# Amis-esp8266d.net
KiCad netlist of a schematic drawn in EAGLE
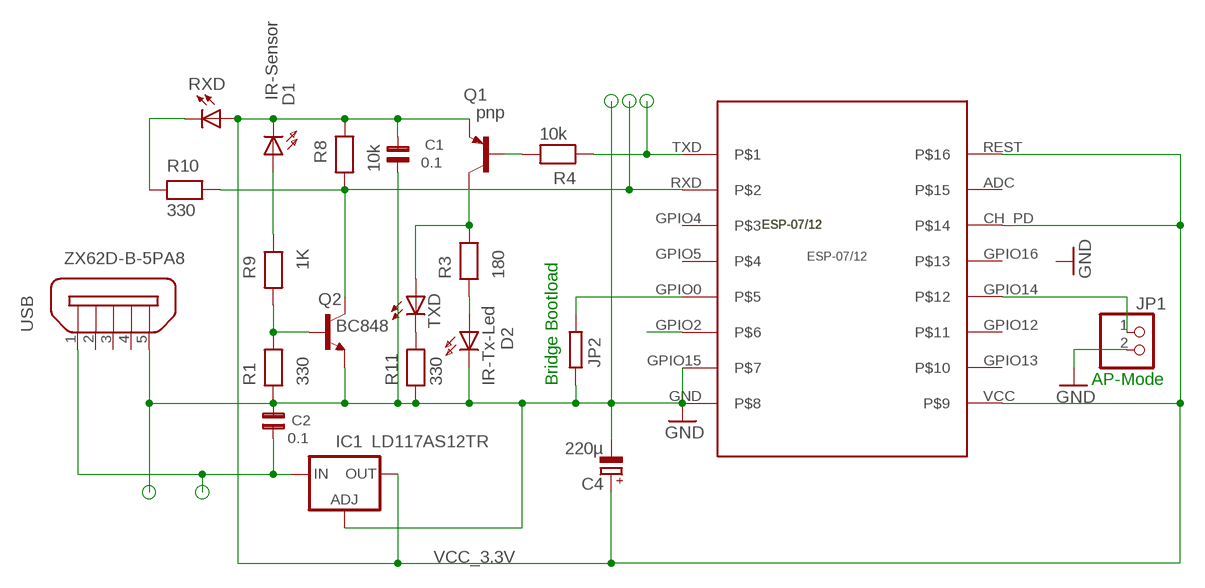
[diagram p0: schematic, sheet 1]

(export (version "E")
  (design (tool "Eeschema 10.0.6"))
  (components
    (comp (ref "C1")
      (value "0.1")
      (footprint "eagle-import:0805W")
      (libsource (lib "eagle-import") (part "C0805W"))
    )
    (comp (ref "C2")
      (value "0.1")
      (footprint "eagle-import:0805W")
      (libsource (lib "eagle-import") (part "C0805W"))
    )
    (comp (ref "C4")
      (value "220µ")
      (footprint "eagle-import:153CLV-0605")
      (libsource (lib "eagle-import") (part "CPOL-EU153CLV-0605"))
    )
    (comp (ref "D1")
      (value "IR-Sensor")
      (footprint "eagle-import:HSMXC670")
      (libsource (lib "eagle-import") (part "HSMXC670"))
    )
    (comp (ref "D2")
      (value "IR-Tx-Led")
      (footprint "eagle-import:HSMXC670")
      (libsource (lib "eagle-import") (part "HSMXC670"))
    )
    (comp (ref "IC1")
      (value "LD117AS12TR")
      (footprint "eagle-import:SOT223")
      (libsource (lib "eagle-import") (part "LD117A?S12TR"))
    )
    (comp (ref "JP1")
      (value "PINHD-1X2")
      (footprint "eagle-import:1X02")
      (libsource (lib "eagle-import") (part "PINHD-1X2"))
    )
    (comp (ref "JP2")
      (value "R-EU_R1210W")
      (footprint "eagle-import:R1210W")
      (libsource (lib "eagle-import") (part "R-EU_R1210W"))
    )
    (comp (ref "Q1")
      (value "pnp")
      (footprint "eagle-import:SOT23")
      (libsource (lib "eagle-import") (part "-?SOT23MMBTA56"))
    )
    (comp (ref "Q2")
      (value "BC848")
      (footprint "eagle-import:SOT23")
      (libsource (lib "eagle-import") (part "BC848"))
    )
    (comp (ref "R1")
      (value "330")
      (footprint "eagle-import:0805W")
      (libsource (lib "eagle-import") (part "R0805W"))
    )
    (comp (ref "R3")
      (value "180")
      (footprint "eagle-import:0805W")
      (libsource (lib "eagle-import") (part "R0805W"))
    )
    (comp (ref "R4")
      (value "10k")
      (footprint "eagle-import:0805W")
      (libsource (lib "eagle-import") (part "R0805W"))
    )
    (comp (ref "R8")
      (value "10k")
      (footprint "eagle-import:0805W")
      (libsource (lib "eagle-import") (part "R0805W"))
    )
    (comp (ref "R9")
      (value "1K")
      (footprint "eagle-import:0805W")
      (libsource (lib "eagle-import") (part "R0805W"))
    )
    (comp (ref "R10")
      (value "330")
      (footprint "eagle-import:0805W")
      (libsource (lib "eagle-import") (part "R0805W"))
    )
    (comp (ref "R11")
      (value "330")
      (footprint "eagle-import:0805W")
      (libsource (lib "eagle-import") (part "R0805W"))
    )
    (comp (ref "RXD")
      (value "LEDSML0805")
      (footprint "eagle-import:SML0805")
      (libsource (lib "eagle-import") (part "LEDSML0805"))
    )
    (comp (ref "TXD")
      (value "LEDSML0805")
      (footprint "eagle-import:SML0805")
      (libsource (lib "eagle-import") (part "LEDSML0805"))
    )
    (comp (ref "U$2")
      (value "ESP-07/12")
      (footprint "eagle-import:ESP-07_12")
      (libsource (lib "eagle-import") (part "ESP-07/12"))
    )
    (comp (ref "USB")
      (value "ZX62D-B-5PA8")
      (footprint "eagle-import:ZX62D-B-5PA8")
      (fields (field (name "MF") "Hirose"))
      (libsource (lib "eagle-import") (part "ZX62D-B-5PA8"))
    )
  )
  (nets
    (net (code "1") (name "/VCC_3.3V") (class "Default")
      (node (ref "C1") (pin "2") (pinfunction "2_2") (pintype "passive"))
      (node (ref "C4") (pin "+") (pinfunction "+_+") (pintype "passive"))
      (node (ref "D1") (pin "K") (pinfunction "C_K") (pintype "passive"))
      (node (ref "IC1") (pin "4") (pinfunction "OUT_4") (pintype "passive"))
      (node (ref "Q1") (pin "2") (pinfunction "E_2") (pintype "passive"))
      (node (ref "R8") (pin "2") (pinfunction "2_2") (pintype "passive"))
      (node (ref "RXD") (pin "A") (pinfunction "A_A") (pintype "passive"))
      (node (ref "U$2") (pin "CH_PD") (pinfunction "P$14_CH_PD") (pintype "bidirectional"))
      (node (ref "U$2") (pin "REST") (pinfunction "P$16_REST") (pintype "bidirectional"))
      (node (ref "U$2") (pin "VCC") (pinfunction "P$9_VCC") (pintype "bidirectional"))
    )
    (net (code "2") (name "GND") (class "Default")
      (node (ref "C1") (pin "1") (pinfunction "1_1") (pintype "passive"))
      (node (ref "C2") (pin "2") (pinfunction "2_2") (pintype "passive"))
      (node (ref "C4") (pin "-") (pinfunction "-_-") (pintype "passive"))
      (node (ref "D2") (pin "K") (pinfunction "C_K") (pintype "passive"))
      (node (ref "IC1") (pin "1") (pinfunction "ADJ_1") (pintype "input"))
      (node (ref "JP1") (pin "2") (pinfunction "2_2") (pintype "passive"))
      (node (ref "JP2") (pin "1") (pinfunction "1_1") (pintype "passive"))
      (node (ref "Q2") (pin "2") (pinfunction "E_2") (pintype "passive"))
      (node (ref "R1") (pin "1") (pinfunction "1_1") (pintype "passive"))
      (node (ref "R11") (pin "1") (pinfunction "1_1") (pintype "passive"))
      (node (ref "U$2") (pin "GND") (pinfunction "P$8_GND") (pintype "bidirectional"))
      (node (ref "U$2") (pin "GPIO15") (pinfunction "P$7_GPIO15") (pintype "bidirectional"))
      (node (ref "USB") (pin "5") (pinfunction "5_5") (pintype "passive"))
    )
    (net (code "3") (name "Net-(D1-PadA)") (class "Default")
      (node (ref "D1") (pin "A") (pinfunction "A_A") (pintype "passive"))
      (node (ref "R9") (pin "2") (pinfunction "2_2") (pintype "passive"))
    )
    (net (code "4") (name "Net-(D2-PadA)") (class "Default")
      (node (ref "D2") (pin "A") (pinfunction "A_A") (pintype "passive"))
      (node (ref "R3") (pin "1") (pinfunction "1_1") (pintype "passive"))
    )
    (net (code "5") (name "Net-(IC1-IN)") (class "Default")
      (node (ref "C2") (pin "1") (pinfunction "1_1") (pintype "passive"))
      (node (ref "IC1") (pin "3") (pinfunction "IN_3") (pintype "input"))
      (node (ref "USB") (pin "1") (pinfunction "1_1") (pintype "passive"))
    )
    (net (code "6") (name "Net-(Q1-B)") (class "Default")
      (node (ref "Q1") (pin "1") (pinfunction "B_1") (pintype "passive"))
      (node (ref "R4") (pin "2") (pinfunction "2_2") (pintype "passive"))
    )
    (net (code "7") (name "Net-(Q1-C)") (class "Default")
      (node (ref "Q1") (pin "3") (pinfunction "C_3") (pintype "passive"))
      (node (ref "R3") (pin "2") (pinfunction "2_2") (pintype "passive"))
      (node (ref "TXD") (pin "A") (pinfunction "A_A") (pintype "passive"))
    )
    (net (code "8") (name "Net-(Q2-B)") (class "Default")
      (node (ref "Q2") (pin "1") (pinfunction "B_1") (pintype "passive"))
      (node (ref "R1") (pin "2") (pinfunction "2_2") (pintype "passive"))
      (node (ref "R9") (pin "1") (pinfunction "1_1") (pintype "passive"))
    )
    (net (code "9") (name "Net-(Q2-C)") (class "Default")
      (node (ref "Q2") (pin "3") (pinfunction "C_3") (pintype "passive"))
      (node (ref "R10") (pin "2") (pinfunction "2_2") (pintype "passive"))
      (node (ref "R8") (pin "1") (pinfunction "1_1") (pintype "passive"))
      (node (ref "U$2") (pin "RXD") (pinfunction "P$2_RXD") (pintype "bidirectional"))
    )
    (net (code "10") (name "Net-(R10-Pad1)") (class "Default")
      (node (ref "R10") (pin "1") (pinfunction "1_1") (pintype "passive"))
      (node (ref "RXD") (pin "C") (pinfunction "C_C") (pintype "passive"))
    )
    (net (code "11") (name "Net-(R11-Pad2)") (class "Default")
      (node (ref "R11") (pin "2") (pinfunction "2_2") (pintype "passive"))
      (node (ref "TXD") (pin "C") (pinfunction "C_C") (pintype "passive"))
    )
    (net (code "12") (name "Net-(U$2-P$1)") (class "Default")
      (node (ref "R4") (pin "1") (pinfunction "1_1") (pintype "passive"))
      (node (ref "U$2") (pin "TXD") (pinfunction "P$1_TXD") (pintype "bidirectional"))
    )
    (net (code "13") (name "Net-(U$2-P$5)") (class "Default")
      (node (ref "JP2") (pin "2") (pinfunction "2_2") (pintype "passive"))
      (node (ref "U$2") (pin "GPIO0") (pinfunction "P$5_GPIO0") (pintype "bidirectional"))
    )
    (net (code "14") (name "Net-(U$2-P$12)") (class "Default")
      (node (ref "JP1") (pin "1") (pinfunction "1_1") (pintype "passive"))
      (node (ref "U$2") (pin "GPIO14") (pinfunction "P$12_GPIO14") (pintype "bidirectional"))
    )
    (net (code "15") (name "unconnected-(U$2-P$3-PadGPIO4)") (class "Default")
      (node (ref "U$2") (pin "GPIO4") (pinfunction "P$3_GPIO4") (pintype "bidirectional"))
    )
    (net (code "16") (name "unconnected-(U$2-P$4-PadGPIO5)") (class "Default")
      (node (ref "U$2") (pin "GPIO5") (pinfunction "P$4_GPIO5") (pintype "bidirectional"))
    )
    (net (code "17") (name "unconnected-(U$2-P$6-PadGPIO2)") (class "Default")
      (node (ref "U$2") (pin "GPIO2") (pinfunction "P$6_GPIO2") (pintype "bidirectional"))
    )
    (net (code "18") (name "unconnected-(U$2-P$10-PadGPIO13)") (class "Default")
      (node (ref "U$2") (pin "GPIO13") (pinfunction "P$10_GPIO13") (pintype "bidirectional"))
    )
    (net (code "19") (name "unconnected-(U$2-P$11-PadGPIO12)") (class "Default")
      (node (ref "U$2") (pin "GPIO12") (pinfunction "P$11_GPIO12") (pintype "bidirectional"))
    )
    (net (code "20") (name "unconnected-(U$2-P$13-PadGPIO16)") (class "Default")
      (node (ref "U$2") (pin "GPIO16") (pinfunction "P$13_GPIO16") (pintype "bidirectional"))
    )
    (net (code "21") (name "unconnected-(U$2-P$15-PadADC)") (class "Default")
      (node (ref "U$2") (pin "ADC") (pinfunction "P$15_ADC") (pintype "bidirectional"))
    )
    (net (code "22") (name "unconnected-(USB-Pad2)") (class "Default")
      (node (ref "USB") (pin "2") (pinfunction "2_2") (pintype "passive"))
    )
    (net (code "23") (name "unconnected-(USB-Pad3)") (class "Default")
      (node (ref "USB") (pin "3") (pinfunction "3_3") (pintype "passive"))
    )
    (net (code "24") (name "unconnected-(USB-Pad4)") (class "Default")
      (node (ref "USB") (pin "4") (pinfunction "4_4") (pintype "passive"))
    )
  )
)
